# icm_cpld.net
KiCad netlist of a schematic drawn in Altium Designer
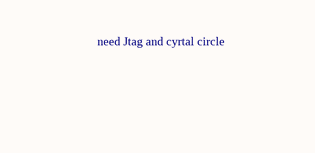
[diagram p0: icm+cpld.SchDoc, top right]
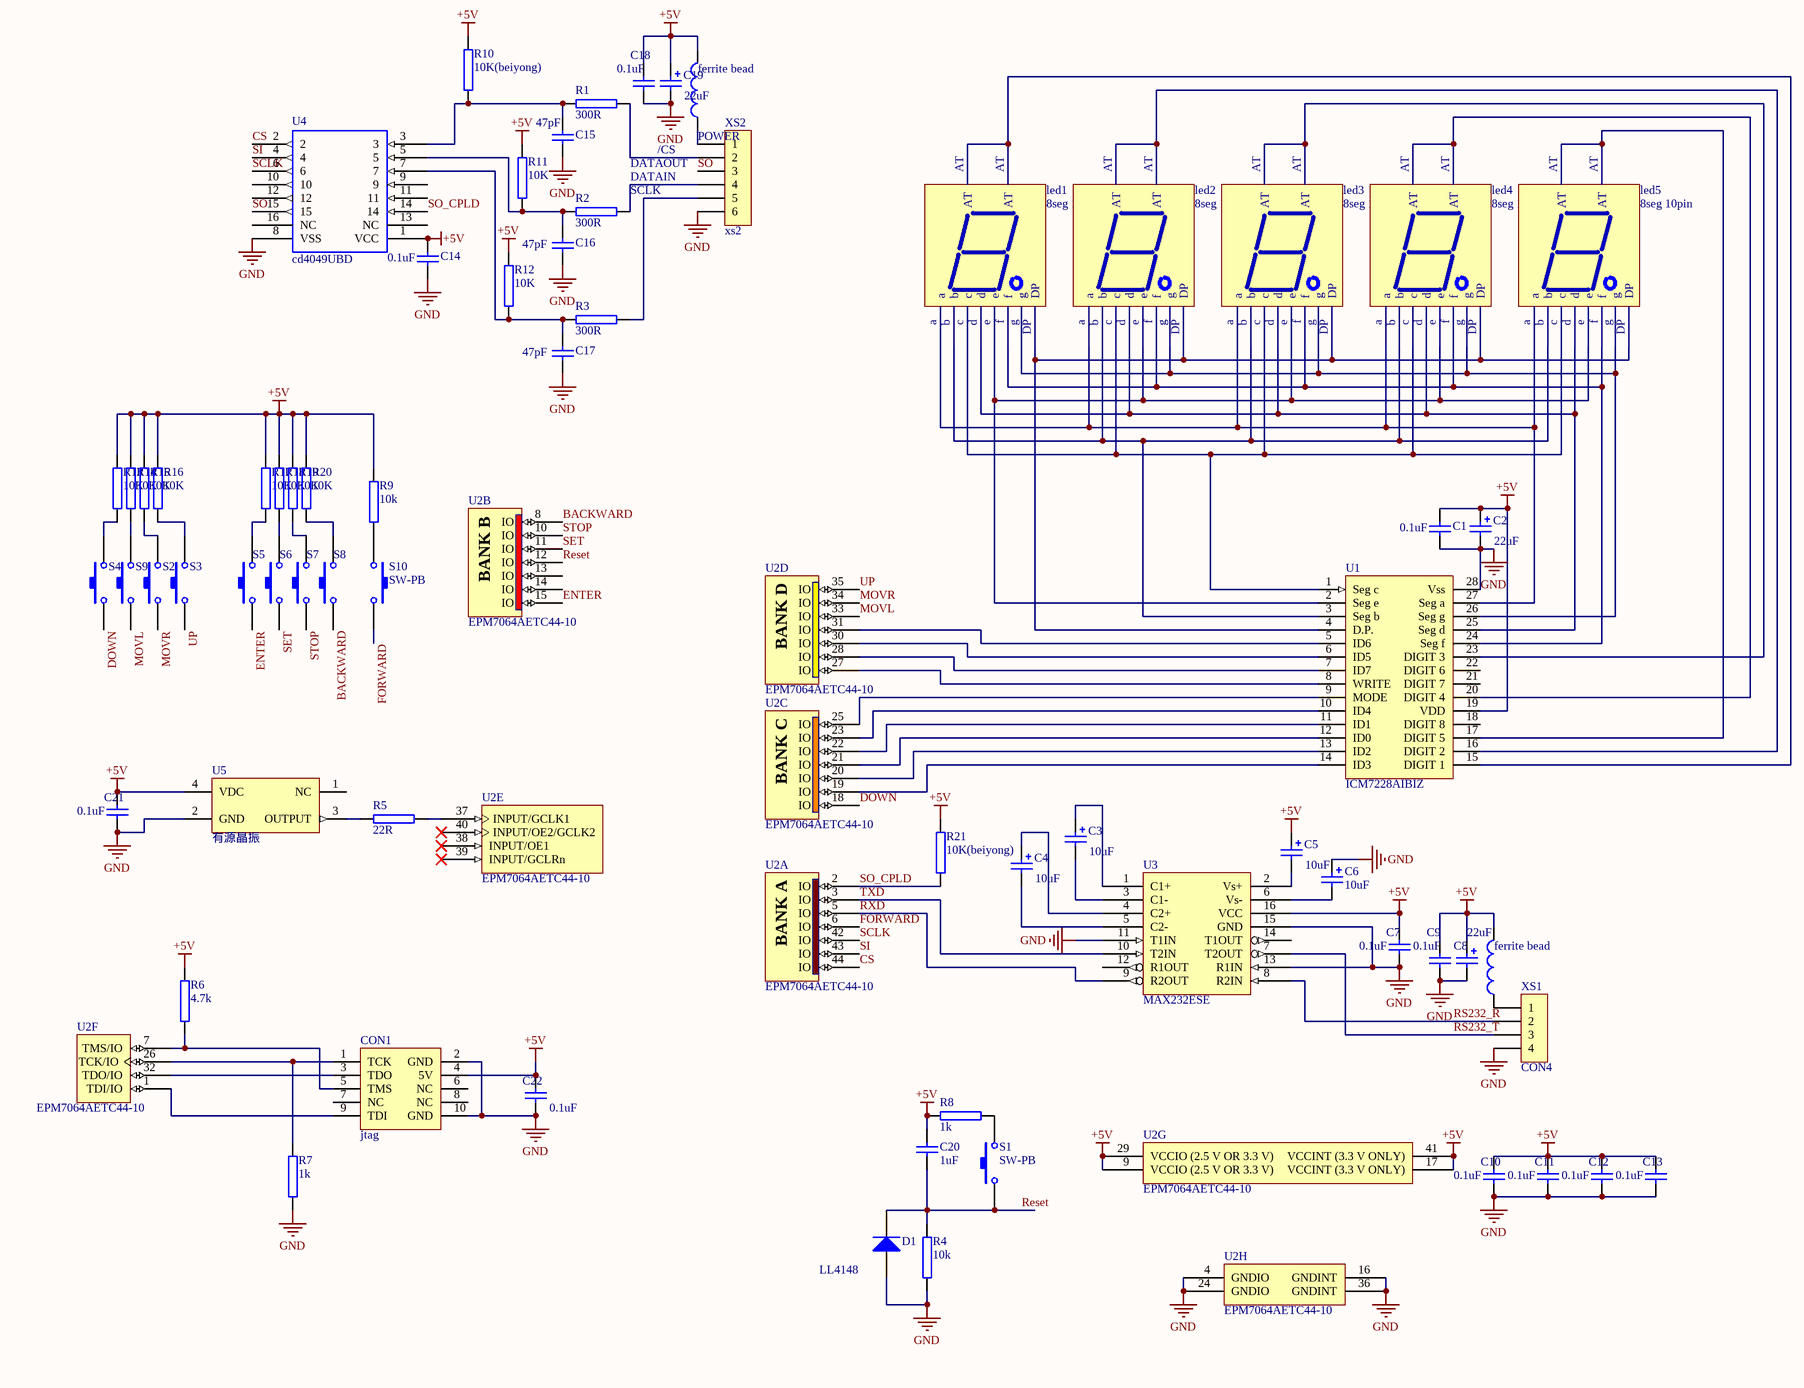
[diagram p1: icm+cpld.SchDoc, bottom left]

(export (version "E")
  (design (tool "Eeschema 10.0.6"))
  (components
    (comp (ref "C1")
      (value "0.1uF")
      (footprint "0805")
      (description "Capacitor")
      (fields (field (name "Comment") "Cap") (field (name "PUBLISHER") "Altium Limited"))
      (libsource (lib "Miscellaneous Devices") (part "Cap"))
    )
    (comp (ref "C2")
      (value "22uF")
      (footprint "7343")
      (description "Polarized Capacitor (Axial)")
      (fields (field (name "PUBLISHER") "Altium Limited"))
      (libsource (lib "Miscellaneous Devices") (part "Cap Pol2"))
    )
    (comp (ref "C3")
      (value "10uF")
      (footprint "C1206")
      (description "Polarized Capacitor (Axial)")
      (fields (field (name "PUBLISHER") "Altium Limited"))
      (libsource (lib "Miscellaneous Devices") (part "Cap Pol2"))
    )
    (comp (ref "C4")
      (value "10uF")
      (footprint "C1206")
      (description "Polarized Capacitor (Axial)")
      (fields (field (name "Comment") "22uF") (field (name "PUBLISHER") "Altium Limited"))
      (libsource (lib "Miscellaneous Devices") (part "Cap Pol2"))
    )
    (comp (ref "C5")
      (value "10uF")
      (footprint "C1206")
      (description "Polarized Capacitor (Axial)")
      (fields (field (name "PUBLISHER") "Altium Limited"))
      (libsource (lib "Miscellaneous Devices") (part "Cap Pol2"))
    )
    (comp (ref "C6")
      (value "10uF")
      (footprint "C1206")
      (description "Polarized Capacitor (Axial)")
      (fields (field (name "PUBLISHER") "Altium Limited"))
      (libsource (lib "Miscellaneous Devices") (part "Cap Pol2"))
    )
    (comp (ref "C7")
      (value "0.1uF")
      (footprint "0805")
      (description "Capacitor")
      (fields (field (name "Comment") "Cap") (field (name "PUBLISHER") "Altium Limited"))
      (libsource (lib "Miscellaneous Devices") (part "Cap"))
    )
    (comp (ref "C8")
      (value "22uF")
      (footprint "7343")
      (description "Polarized Capacitor (Axial)")
      (fields (field (name "PUBLISHER") "Altium Limited"))
      (libsource (lib "Miscellaneous Devices") (part "Cap Pol2"))
    )
    (comp (ref "C9")
      (value "0.1uF")
      (footprint "0805")
      (description "Capacitor")
      (fields (field (name "Comment") "Cap") (field (name "PUBLISHER") "Altium Limited"))
      (libsource (lib "Miscellaneous Devices") (part "Cap"))
    )
    (comp (ref "C10")
      (value "0.1uF")
      (footprint "0805")
      (description "Capacitor")
      (fields (field (name "Comment") "Cap") (field (name "PUBLISHER") "Altium Limited"))
      (libsource (lib "Miscellaneous Devices") (part "Cap"))
    )
    (comp (ref "C11")
      (value "0.1uF")
      (footprint "0805")
      (description "Capacitor")
      (fields (field (name "Comment") "Cap") (field (name "PUBLISHER") "Altium Limited"))
      (libsource (lib "Miscellaneous Devices") (part "Cap"))
    )
    (comp (ref "C12")
      (value "0.1uF")
      (footprint "0805")
      (description "Capacitor")
      (fields (field (name "Comment") "Cap") (field (name "PUBLISHER") "Altium Limited"))
      (libsource (lib "Miscellaneous Devices") (part "Cap"))
    )
    (comp (ref "C13")
      (value "0.1uF")
      (footprint "0805")
      (description "Capacitor")
      (fields (field (name "Comment") "Cap") (field (name "PUBLISHER") "Altium Limited"))
      (libsource (lib "Miscellaneous Devices") (part "Cap"))
    )
    (comp (ref "C14")
      (value "0.1uF")
      (footprint "0805")
      (description "Capacitor")
      (fields (field (name "Comment") "Cap") (field (name "PUBLISHER") "Altium Limited"))
      (libsource (lib "Miscellaneous Devices") (part "Cap"))
    )
    (comp (ref "C15")
      (value "47pF")
      (footprint "0805")
      (description "Capacitor")
      (fields (field (name "Comment") "Cap") (field (name "PUBLISHER") "Altium Limited"))
      (libsource (lib "Miscellaneous Devices") (part "Cap"))
    )
    (comp (ref "C16")
      (value "47pF")
      (footprint "0805")
      (description "Capacitor")
      (fields (field (name "Comment") "Cap") (field (name "PUBLISHER") "Altium Limited"))
      (libsource (lib "Miscellaneous Devices") (part "Cap"))
    )
    (comp (ref "C17")
      (value "47pF")
      (footprint "0805")
      (description "Capacitor")
      (fields (field (name "Comment") "Cap") (field (name "PUBLISHER") "Altium Limited"))
      (libsource (lib "Miscellaneous Devices") (part "Cap"))
    )
    (comp (ref "C18")
      (value "0.1uF")
      (footprint "0805")
      (description "Capacitor")
      (fields (field (name "Comment") "Cap") (field (name "PUBLISHER") "Altium Limited"))
      (libsource (lib "Miscellaneous Devices") (part "Cap"))
    )
    (comp (ref "C19")
      (value "22uF")
      (footprint "7343")
      (description "Polarized Capacitor (Axial)")
      (fields (field (name "PUBLISHER") "Altium Limited"))
      (libsource (lib "Miscellaneous Devices") (part "Cap Pol2"))
    )
    (comp (ref "C20")
      (value "1uF")
      (footprint "1206")
      (description "Capacitor")
      (fields (field (name "Comment") "Cap") (field (name "PUBLISHER") "Altium Limited"))
      (libsource (lib "Miscellaneous Devices") (part "Cap"))
    )
    (comp (ref "C21")
      (value "0.1uF")
      (footprint "0805")
      (description "Capacitor")
      (fields (field (name "Comment") "Cap") (field (name "PUBLISHER") "Altium Limited"))
      (libsource (lib "Miscellaneous Devices") (part "Cap"))
    )
    (comp (ref "C22")
      (value "0.1uF")
      (footprint "0805")
      (description "Capacitor")
      (fields (field (name "Comment") "Cap") (field (name "PUBLISHER") "Altium Limited"))
      (libsource (lib "Miscellaneous Devices") (part "Cap"))
    )
    (comp (ref "CON1") (value "jtag") (footprint "HDR2X5") (libsource (lib "display_1") (part "jtag")))
    (comp (ref "D1")
      (value "LL4148")
      (footprint "DO214")
      (description "High Conductance Fast Diode")
      (fields (field (name "PUBLISHER") "Altium Limited"))
      (libsource (lib "Miscellaneous Devices") (part "Diode 1N4148"))
    )
    (comp (ref "L1") (value "ferrite bead") (footprint "0805") (libsource (lib "display") (part "INDUCTOR")))
    (comp (ref "L2") (value "ferrite bead") (footprint "0805") (libsource (lib "display") (part "INDUCTOR")))
    (comp (ref "led1")
      (value "8seg 10pin")
      (footprint "LEDsum")
      (libsource (lib "display_1") (part "8seg 10pin"))
    )
    (comp (ref "led2")
      (value "8seg 10pin")
      (footprint "LEDsum")
      (libsource (lib "display_1") (part "8seg 10pin"))
    )
    (comp (ref "led3")
      (value "8seg 10pin")
      (footprint "LEDsum")
      (libsource (lib "display_1") (part "8seg 10pin"))
    )
    (comp (ref "led4")
      (value "8seg 10pin")
      (footprint "LEDsum")
      (libsource (lib "display_1") (part "8seg 10pin"))
    )
    (comp (ref "led5")
      (value "8seg 10pin")
      (footprint "LEDsum")
      (libsource (lib "display_1") (part "8seg 10pin"))
    )
    (comp (ref "R1")
      (value "300R")
      (footprint "³£ÓÃÔª¼þ·âÑbì(pcb):0805")
      (libsource (lib "2CPU") (part "RES2"))
    )
    (comp (ref "R2") (value "300R") (footprint "0805") (libsource (lib "2CPU") (part "RES2")))
    (comp (ref "R3") (value "300R") (footprint "0805") (libsource (lib "2CPU") (part "RES2")))
    (comp (ref "R4") (value "10k") (footprint "0805") (libsource (lib "2CPU") (part "RES2")))
    (comp (ref "R5") (value "22R") (footprint "0805") (libsource (lib "2CPU") (part "RES2")))
    (comp (ref "R6") (value "4.7k") (footprint "0805") (libsource (lib "2CPU") (part "RES2")))
    (comp (ref "R7") (value "1k") (footprint "0805") (libsource (lib "2CPU") (part "RES2")))
    (comp (ref "R8") (value "1k") (footprint "0805") (libsource (lib "2CPU") (part "RES2")))
    (comp (ref "R9") (value "10k") (footprint "0805") (libsource (lib "2CPU") (part "RES2")))
    (comp (ref "R10")
      (value "10K(beiyong)")
      (footprint "³£ÓÃÔª¼þ·âÑbì(pcb):0805")
      (libsource (lib "2CPU") (part "RES2"))
    )
    (comp (ref "R11")
      (value "10K")
      (footprint "³£ÓÃÔª¼þ·âÑbì(pcb):0805")
      (libsource (lib "2CPU") (part "RES2"))
    )
    (comp (ref "R12")
      (value "10K")
      (footprint "³£ÓÃÔª¼þ·âÑbì(pcb):0805")
      (libsource (lib "2CPU") (part "RES2"))
    )
    (comp (ref "R13")
      (value "10K")
      (footprint "³£ÓÃÔª¼þ·âÑbì(pcb):0805")
      (libsource (lib "2CPU") (part "RES2"))
    )
    (comp (ref "R14")
      (value "10K")
      (footprint "³£ÓÃÔª¼þ·âÑbì(pcb):0805")
      (libsource (lib "2CPU") (part "RES2"))
    )
    (comp (ref "R15")
      (value "10K")
      (footprint "³£ÓÃÔª¼þ·âÑbì(pcb):0805")
      (libsource (lib "2CPU") (part "RES2"))
    )
    (comp (ref "R16")
      (value "10K")
      (footprint "³£ÓÃÔª¼þ·âÑbì(pcb):0805")
      (libsource (lib "2CPU") (part "RES2"))
    )
    (comp (ref "R17")
      (value "10K")
      (footprint "³£ÓÃÔª¼þ·âÑbì(pcb):0805")
      (libsource (lib "2CPU") (part "RES2"))
    )
    (comp (ref "R18")
      (value "10K")
      (footprint "³£ÓÃÔª¼þ·âÑbì(pcb):0805")
      (libsource (lib "2CPU") (part "RES2"))
    )
    (comp (ref "R19")
      (value "10K")
      (footprint "³£ÓÃÔª¼þ·âÑbì(pcb):0805")
      (libsource (lib "2CPU") (part "RES2"))
    )
    (comp (ref "R20")
      (value "10K")
      (footprint "³£ÓÃÔª¼þ·âÑbì(pcb):0805")
      (libsource (lib "2CPU") (part "RES2"))
    )
    (comp (ref "R21")
      (value "10K(beiyong)")
      (footprint "³£ÓÃÔª¼þ·âÑbì(pcb):0805")
      (libsource (lib "2CPU") (part "RES2"))
    )
    (comp (ref "S1")
      (value "SW-PB")
      (footprint "PcbLib1:reset")
      (description "Switch")
      (fields (field (name "PUBLISHER") "Altium Limited"))
      (libsource (lib "Miscellaneous Devices") (part "SW-PB"))
    )
    (comp (ref "S2")
      (value "SW-PB")
      (footprint "PcbLib1:B3F4050")
      (description "Switch")
      (fields (field (name "PUBLISHER") "Altium Limited"))
      (libsource (lib "Miscellaneous Devices") (part "SW-PB"))
    )
    (comp (ref "S3")
      (value "SW-PB")
      (footprint "PcbLib1:B3F4050")
      (description "Switch")
      (fields (field (name "PUBLISHER") "Altium Limited"))
      (libsource (lib "Miscellaneous Devices") (part "SW-PB"))
    )
    (comp (ref "S4")
      (value "SW-PB")
      (footprint "PcbLib1:B3F4050")
      (description "Switch")
      (fields (field (name "PUBLISHER") "Altium Limited"))
      (libsource (lib "Miscellaneous Devices") (part "SW-PB"))
    )
    (comp (ref "S5")
      (value "SW-PB")
      (footprint "PcbLib1:B3F4050")
      (description "Switch")
      (fields (field (name "PUBLISHER") "Altium Limited"))
      (libsource (lib "Miscellaneous Devices") (part "SW-PB"))
    )
    (comp (ref "S6")
      (value "SW-PB")
      (footprint "PcbLib1:B3F4050")
      (description "Switch")
      (fields (field (name "PUBLISHER") "Altium Limited"))
      (libsource (lib "Miscellaneous Devices") (part "SW-PB"))
    )
    (comp (ref "S7")
      (value "SW-PB")
      (footprint "PcbLib1:B3F4050")
      (description "Switch")
      (fields (field (name "PUBLISHER") "Altium Limited"))
      (libsource (lib "Miscellaneous Devices") (part "SW-PB"))
    )
    (comp (ref "S8")
      (value "SW-PB")
      (footprint "PcbLib1:B3F4050")
      (description "Switch")
      (fields (field (name "PUBLISHER") "Altium Limited"))
      (libsource (lib "Miscellaneous Devices") (part "SW-PB"))
    )
    (comp (ref "S9")
      (value "SW-PB")
      (footprint "PcbLib1:B3F4050")
      (description "Switch")
      (fields (field (name "PUBLISHER") "Altium Limited"))
      (libsource (lib "Miscellaneous Devices") (part "SW-PB"))
    )
    (comp (ref "S10")
      (value "SW-PB")
      (footprint "B3F4050")
      (description "Switch")
      (fields (field (name "PUBLISHER") "Altium Limited"))
      (libsource (lib "Miscellaneous Devices") (part "SW-PB"))
    )
    (comp (ref "U1") (value "ICM7228AIBIZ") (footprint "SO28_L") (libsource (lib "lib") (part "ICM7218")))
    (comp (ref "U2")
      (value "EPM7064AETC44-10")
      (footprint "TQFP44_N")
      (description "MAX 7000AE 3.3V CPLD, 64 Macrocells, 44-Pin TQFP, Speed Grade 10, Commercial Grade")
      (fields (field (name "PUBLISHER") "Altium Limited"))
      (libsource (lib "Altera MAX 7000AE") (part "EPM7064AETC44-10"))
    )
    (comp (ref "U3")
      (value "MAX232ESE")
      (footprint "NSO16_N")
      (description "DUAL EIA-232 DRIVER/RECEIVER")
      (libsource (lib "2CPU") (part "MAX232"))
    )
    (comp (ref "U4") (value "cd4049UBD") (footprint "L16_N") (libsource (lib "display_1") (part "cd4049")))
    (comp (ref "U5") (value "有源晶振") (footprint "smd7050") (libsource (lib "display_1") (part "jingzhen")))
    (comp (ref "XS1")
      (value "CON4")
      (footprint "2SIP4")
      (description "Connector")
      (libsource (lib "2CPU") (part "CON4"))
    )
    (comp (ref "XS2") (value "xs2") (footprint "SIP6") (libsource (lib "display") (part "xs6")))
  )
  (nets
    (net (code "1") (name "+5V") (class "Default")
      (node (ref "C1") (pin "2") (pinfunction "2_2") (pintype "passive"))
      (node (ref "C10") (pin "2") (pinfunction "2_2") (pintype "passive"))
      (node (ref "C11") (pin "2") (pinfunction "2_2") (pintype "passive"))
      (node (ref "C12") (pin "2") (pinfunction "2_2") (pintype "passive"))
      (node (ref "C13") (pin "2") (pinfunction "2_2") (pintype "passive"))
      (node (ref "C14") (pin "2") (pinfunction "2_2") (pintype "passive"))
      (node (ref "C18") (pin "2") (pinfunction "2_2") (pintype "passive"))
      (node (ref "C19") (pin "1") (pinfunction "1_1") (pintype "passive"))
      (node (ref "C2") (pin "1") (pinfunction "1_1") (pintype "passive"))
      (node (ref "C20") (pin "1") (pinfunction "1_1") (pintype "passive"))
      (node (ref "C21") (pin "2") (pinfunction "2_2") (pintype "passive"))
      (node (ref "C22") (pin "2") (pinfunction "2_2") (pintype "passive"))
      (node (ref "C5") (pin "1") (pinfunction "1_1") (pintype "passive"))
      (node (ref "C7") (pin "2") (pinfunction "2_2") (pintype "passive"))
      (node (ref "C8") (pin "1") (pinfunction "1_1") (pintype "passive"))
      (node (ref "C9") (pin "2") (pinfunction "2_2") (pintype "passive"))
      (node (ref "CON1") (pin "4") (pinfunction "5V_4") (pintype "power_in"))
      (node (ref "L1") (pin "1") (pinfunction "1_1") (pintype "passive"))
      (node (ref "L2") (pin "1") (pinfunction "1_1") (pintype "passive"))
      (node (ref "R10") (pin "2") (pinfunction "2_2") (pintype "passive"))
      (node (ref "R11") (pin "2") (pinfunction "2_2") (pintype "passive"))
      (node (ref "R12") (pin "2") (pinfunction "2_2") (pintype "passive"))
      (node (ref "R13") (pin "2") (pinfunction "2_2") (pintype "passive"))
      (node (ref "R14") (pin "2") (pinfunction "2_2") (pintype "passive"))
      (node (ref "R15") (pin "2") (pinfunction "2_2") (pintype "passive"))
      (node (ref "R16") (pin "2") (pinfunction "2_2") (pintype "passive"))
      (node (ref "R17") (pin "2") (pinfunction "2_2") (pintype "passive"))
      (node (ref "R18") (pin "2") (pinfunction "2_2") (pintype "passive"))
      (node (ref "R19") (pin "2") (pinfunction "2_2") (pintype "passive"))
      (node (ref "R20") (pin "2") (pinfunction "2_2") (pintype "passive"))
      (node (ref "R21") (pin "2") (pinfunction "2_2") (pintype "passive"))
      (node (ref "R6") (pin "1") (pinfunction "1_1") (pintype "passive"))
      (node (ref "R8") (pin "2") (pinfunction "2_2") (pintype "passive"))
      (node (ref "R9") (pin "1") (pinfunction "1_1") (pintype "passive"))
      (node (ref "U1") (pin "19") (pinfunction "VDD_19") (pintype "passive"))
      (node (ref "U2") (pin "17") (pinfunction "VCCINT_(3.3_V_ONLY)_17") (pintype "power_in"))
      (node (ref "U2") (pin "29") (pinfunction "VCCIO_(2.5_V_OR_3.3_V)_29") (pintype "power_in"))
      (node (ref "U2") (pin "41") (pinfunction "VCCINT_(3.3_V_ONLY)_41") (pintype "power_in"))
      (node (ref "U2") (pin "9") (pinfunction "VCCIO_(2.5_V_OR_3.3_V)_9") (pintype "power_in"))
      (node (ref "U3") (pin "16") (pinfunction "VCC_16") (pintype "power_in"))
      (node (ref "U4") (pin "1") (pinfunction "VCC_1") (pintype "power_in"))
      (node (ref "U5") (pin "4") (pinfunction "VDC_4") (pintype "power_in"))
    )
    (net (code "2") (name "/BACKWARD") (class "Default")
      (node (ref "S8") (pin "1") (pinfunction "1_1") (pintype "passive"))
      (node (ref "U2") (pin "8") (pinfunction "IO_8") (pintype "bidirectional"))
    )
    (net (code "3") (name "/CS") (class "Default")
      (node (ref "U2") (pin "44") (pinfunction "IO_44") (pintype "bidirectional"))
      (node (ref "U4") (pin "2") (pinfunction "2_2") (pintype "output"))
    )
    (net (code "4") (name "/DOWN") (class "Default")
      (node (ref "S4") (pin "1") (pinfunction "1_1") (pintype "passive"))
      (node (ref "U2") (pin "18") (pinfunction "IO_18") (pintype "bidirectional"))
    )
    (net (code "5") (name "/ENTER") (class "Default")
      (node (ref "S5") (pin "1") (pinfunction "1_1") (pintype "passive"))
      (node (ref "U2") (pin "15") (pinfunction "IO_15") (pintype "bidirectional"))
    )
    (net (code "6") (name "/FORWARD") (class "Default")
      (node (ref "S10") (pin "2") (pinfunction "2_2") (pintype "passive"))
      (node (ref "U2") (pin "6") (pinfunction "IO_6") (pintype "bidirectional"))
    )
    (net (code "7") (name "/MOVL") (class "Default")
      (node (ref "S9") (pin "1") (pinfunction "1_1") (pintype "passive"))
      (node (ref "U2") (pin "33") (pinfunction "IO_33") (pintype "bidirectional"))
    )
    (net (code "8") (name "/MOVR") (class "Default")
      (node (ref "S2") (pin "1") (pinfunction "1_1") (pintype "passive"))
      (node (ref "U2") (pin "34") (pinfunction "IO_34") (pintype "bidirectional"))
    )
    (net (code "9") (name "/RS232_R") (class "Default")
      (node (ref "U3") (pin "8") (pinfunction "R2IN_8") (pintype "input"))
      (node (ref "XS1") (pin "2") (pinfunction "2_2") (pintype "passive"))
    )
    (net (code "10") (name "/RS232_T") (class "Default")
      (node (ref "U3") (pin "7") (pinfunction "T2OUT_7") (pintype "output"))
      (node (ref "XS1") (pin "3") (pinfunction "3_3") (pintype "passive"))
    )
    (net (code "11") (name "/RXD") (class "Default")
      (node (ref "U2") (pin "5") (pinfunction "IO_5") (pintype "bidirectional"))
      (node (ref "U3") (pin "9") (pinfunction "R2OUT_9") (pintype "output"))
    )
    (net (code "12") (name "/Reset") (class "Default")
      (node (ref "C20") (pin "2") (pinfunction "2_2") (pintype "passive"))
      (node (ref "D1") (pin "2") (pinfunction "K_2") (pintype "passive"))
      (node (ref "R4") (pin "2") (pinfunction "2_2") (pintype "passive"))
      (node (ref "S1") (pin "1") (pinfunction "1_1") (pintype "passive"))
      (node (ref "U2") (pin "12") (pinfunction "IO_12") (pintype "bidirectional"))
    )
    (net (code "13") (name "/SCLK") (class "Default")
      (node (ref "U2") (pin "42") (pinfunction "IO_42") (pintype "bidirectional"))
      (node (ref "U4") (pin "6") (pinfunction "6_6") (pintype "output"))
    )
    (net (code "14") (name "/SET") (class "Default")
      (node (ref "S6") (pin "1") (pinfunction "1_1") (pintype "passive"))
      (node (ref "U2") (pin "11") (pinfunction "IO_11") (pintype "bidirectional"))
    )
    (net (code "15") (name "/SI") (class "Default")
      (node (ref "U2") (pin "43") (pinfunction "IO_43") (pintype "bidirectional"))
      (node (ref "U4") (pin "4") (pinfunction "4_4") (pintype "output"))
    )
    (net (code "16") (name "/SO") (class "Default")
      (node (ref "U4") (pin "15") (pinfunction "15_15") (pintype "output"))
      (node (ref "XS2") (pin "3") (pinfunction "3_3") (pintype "passive"))
    )
    (net (code "17") (name "/SO_CPLD") (class "Default")
      (node (ref "R21") (pin "1") (pinfunction "1_1") (pintype "passive"))
      (node (ref "U2") (pin "2") (pinfunction "IO_2") (pintype "bidirectional"))
      (node (ref "U4") (pin "14") (pinfunction "14_14") (pintype "input"))
    )
    (net (code "18") (name "/STOP") (class "Default")
      (node (ref "S7") (pin "1") (pinfunction "1_1") (pintype "passive"))
      (node (ref "U2") (pin "10") (pinfunction "IO_10") (pintype "bidirectional"))
    )
    (net (code "19") (name "/TXD") (class "Default")
      (node (ref "U2") (pin "3") (pinfunction "IO_3") (pintype "bidirectional"))
      (node (ref "U3") (pin "10") (pinfunction "T2IN_10") (pintype "input"))
    )
    (net (code "20") (name "/UP") (class "Default")
      (node (ref "S3") (pin "1") (pinfunction "1_1") (pintype "passive"))
      (node (ref "U2") (pin "35") (pinfunction "IO_35") (pintype "bidirectional"))
    )
    (net (code "21") (name "GND") (class "Default")
      (node (ref "C1") (pin "1") (pinfunction "1_1") (pintype "passive"))
      (node (ref "C10") (pin "1") (pinfunction "1_1") (pintype "passive"))
      (node (ref "C11") (pin "1") (pinfunction "1_1") (pintype "passive"))
      (node (ref "C12") (pin "1") (pinfunction "1_1") (pintype "passive"))
      (node (ref "C13") (pin "1") (pinfunction "1_1") (pintype "passive"))
      (node (ref "C14") (pin "1") (pinfunction "1_1") (pintype "passive"))
      (node (ref "C15") (pin "1") (pinfunction "1_1") (pintype "passive"))
      (node (ref "C16") (pin "1") (pinfunction "1_1") (pintype "passive"))
      (node (ref "C17") (pin "1") (pinfunction "1_1") (pintype "passive"))
      (node (ref "C18") (pin "1") (pinfunction "1_1") (pintype "passive"))
      (node (ref "C19") (pin "2") (pinfunction "2_2") (pintype "passive"))
      (node (ref "C2") (pin "2") (pinfunction "2_2") (pintype "passive"))
      (node (ref "C21") (pin "1") (pinfunction "1_1") (pintype "passive"))
      (node (ref "C22") (pin "1") (pinfunction "1_1") (pintype "passive"))
      (node (ref "C6") (pin "1") (pinfunction "1_1") (pintype "passive"))
      (node (ref "C7") (pin "1") (pinfunction "1_1") (pintype "passive"))
      (node (ref "C8") (pin "2") (pinfunction "2_2") (pintype "passive"))
      (node (ref "C9") (pin "1") (pinfunction "1_1") (pintype "passive"))
      (node (ref "CON1") (pin "10") (pinfunction "GND_10") (pintype "power_in"))
      (node (ref "CON1") (pin "2") (pinfunction "GND_2") (pintype "power_in"))
      (node (ref "D1") (pin "1") (pinfunction "A_1") (pintype "passive"))
      (node (ref "R4") (pin "1") (pinfunction "1_1") (pintype "passive"))
      (node (ref "R7") (pin "2") (pinfunction "2_2") (pintype "passive"))
      (node (ref "U1") (pin "28") (pinfunction "Vss_28") (pintype "passive"))
      (node (ref "U2") (pin "16") (pinfunction "GNDINT_16") (pintype "power_in"))
      (node (ref "U2") (pin "24") (pinfunction "GNDIO_24") (pintype "power_in"))
      (node (ref "U2") (pin "36") (pinfunction "GNDINT_36") (pintype "power_in"))
      (node (ref "U2") (pin "4") (pinfunction "GNDIO_4") (pintype "power_in"))
      (node (ref "U3") (pin "11") (pinfunction "T1IN_11") (pintype "input"))
      (node (ref "U3") (pin "13") (pinfunction "R1IN_13") (pintype "input"))
      (node (ref "U3") (pin "15") (pinfunction "GND_15") (pintype "power_in"))
      (node (ref "U4") (pin "8") (pinfunction "VSS_8") (pintype "power_in"))
      (node (ref "U5") (pin "2") (pinfunction "GND_2") (pintype "power_in"))
      (node (ref "XS1") (pin "4") (pinfunction "4_4") (pintype "passive"))
      (node (ref "XS2") (pin "6") (pinfunction "6_6") (pintype "passive"))
    )
    (net (code "22") (name "Net-(C15-Pad2)") (class "Default")
      (node (ref "C15") (pin "2") (pinfunction "2_2") (pintype "passive"))
      (node (ref "R1") (pin "1") (pinfunction "1_1") (pintype "passive"))
      (node (ref "R10") (pin "1") (pinfunction "1_1") (pintype "passive"))
      (node (ref "U4") (pin "3") (pinfunction "3_3") (pintype "input"))
    )
    (net (code "23") (name "Net-(C16-Pad2)") (class "Default")
      (node (ref "C16") (pin "2") (pinfunction "2_2") (pintype "passive"))
      (node (ref "R11") (pin "1") (pinfunction "1_1") (pintype "passive"))
      (node (ref "R2") (pin "1") (pinfunction "1_1") (pintype "passive"))
      (node (ref "U4") (pin "5") (pinfunction "5_5") (pintype "input"))
    )
    (net (code "24") (name "Net-(C17-Pad2)") (class "Default")
      (node (ref "C17") (pin "2") (pinfunction "2_2") (pintype "passive"))
      (node (ref "R12") (pin "1") (pinfunction "1_1") (pintype "passive"))
      (node (ref "R3") (pin "1") (pinfunction "1_1") (pintype "passive"))
      (node (ref "U4") (pin "7") (pinfunction "7_7") (pintype "input"))
    )
    (net (code "25") (name "Net-(CON1-TCK)") (class "Default")
      (node (ref "CON1") (pin "1") (pinfunction "TCK_1") (pintype "passive"))
      (node (ref "R7") (pin "1") (pinfunction "1_1") (pintype "passive"))
      (node (ref "U2") (pin "26") (pinfunction "TCK/IO_26") (pintype "bidirectional"))
    )
    (net (code "26") (name "Net-(CON1-TDI)") (class "Default")
      (node (ref "CON1") (pin "9") (pinfunction "TDI_9") (pintype "passive"))
      (node (ref "U2") (pin "1") (pinfunction "TDI/IO_1") (pintype "bidirectional"))
    )
    (net (code "27") (name "Net-(CON1-TDO)") (class "Default")
      (node (ref "CON1") (pin "3") (pinfunction "TDO_3") (pintype "passive"))
      (node (ref "U2") (pin "32") (pinfunction "TDO/IO_32") (pintype "bidirectional"))
    )
    (net (code "28") (name "Net-(CON1-TMS)") (class "Default")
      (node (ref "CON1") (pin "5") (pinfunction "TMS_5") (pintype "passive"))
      (node (ref "R6") (pin "2") (pinfunction "2_2") (pintype "passive"))
      (node (ref "U2") (pin "7") (pinfunction "TMS/IO_7") (pintype "bidirectional"))
    )
    (net (code "29") (name "Net-(L1-Pad2)") (class "Default")
      (node (ref "L1") (pin "2") (pinfunction "2_2") (pintype "passive"))
      (node (ref "XS1") (pin "1") (pinfunction "1_1") (pintype "passive"))
    )
    (net (code "30") (name "Net-(L2-Pad2)") (class "Default")
      (node (ref "L2") (pin "2") (pinfunction "2_2") (pintype "passive"))
      (node (ref "XS2") (pin "1") (pinfunction "1_1") (pintype "passive"))
    )
    (net (code "31") (name "Net-(R1-Pad2)") (class "Default")
      (node (ref "R1") (pin "2") (pinfunction "2_2") (pintype "passive"))
      (node (ref "XS2") (pin "2") (pinfunction "2_2") (pintype "passive"))
    )
    (net (code "32") (name "Net-(R2-Pad2)") (class "Default")
      (node (ref "R2") (pin "2") (pinfunction "2_2") (pintype "passive"))
      (node (ref "XS2") (pin "4") (pinfunction "4_4") (pintype "passive"))
    )
    (net (code "33") (name "Net-(R3-Pad2)") (class "Default")
      (node (ref "R3") (pin "2") (pinfunction "2_2") (pintype "passive"))
      (node (ref "XS2") (pin "5") (pinfunction "5_5") (pintype "passive"))
    )
    (net (code "34") (name "Net-(R8-Pad1)") (class "Default")
      (node (ref "R8") (pin "1") (pinfunction "1_1") (pintype "passive"))
      (node (ref "S1") (pin "2") (pinfunction "2_2") (pintype "passive"))
    )
    (net (code "35") (name "Net-(R9-Pad2)") (class "Default")
      (node (ref "R9") (pin "2") (pinfunction "2_2") (pintype "passive"))
      (node (ref "S10") (pin "1") (pinfunction "1_1") (pintype "passive"))
    )
    (net (code "36") (name "Net-(R13-Pad1)") (class "Default")
      (node (ref "R13") (pin "1") (pinfunction "1_1") (pintype "passive"))
      (node (ref "S4") (pin "2") (pinfunction "2_2") (pintype "passive"))
    )
    (net (code "37") (name "Net-(R14-Pad1)") (class "Default")
      (node (ref "R14") (pin "1") (pinfunction "1_1") (pintype "passive"))
      (node (ref "S9") (pin "2") (pinfunction "2_2") (pintype "passive"))
    )
    (net (code "38") (name "Net-(R15-Pad1)") (class "Default")
      (node (ref "R15") (pin "1") (pinfunction "1_1") (pintype "passive"))
      (node (ref "S2") (pin "2") (pinfunction "2_2") (pintype "passive"))
    )
    (net (code "39") (name "Net-(R16-Pad1)") (class "Default")
      (node (ref "R16") (pin "1") (pinfunction "1_1") (pintype "passive"))
      (node (ref "S3") (pin "2") (pinfunction "2_2") (pintype "passive"))
    )
    (net (code "40") (name "Net-(R17-Pad1)") (class "Default")
      (node (ref "R17") (pin "1") (pinfunction "1_1") (pintype "passive"))
      (node (ref "S5") (pin "2") (pinfunction "2_2") (pintype "passive"))
    )
    (net (code "41") (name "Net-(R18-Pad1)") (class "Default")
      (node (ref "R18") (pin "1") (pinfunction "1_1") (pintype "passive"))
      (node (ref "S6") (pin "2") (pinfunction "2_2") (pintype "passive"))
    )
    (net (code "42") (name "Net-(R19-Pad1)") (class "Default")
      (node (ref "R19") (pin "1") (pinfunction "1_1") (pintype "passive"))
      (node (ref "S7") (pin "2") (pinfunction "2_2") (pintype "passive"))
    )
    (net (code "43") (name "Net-(R20-Pad1)") (class "Default")
      (node (ref "R20") (pin "1") (pinfunction "1_1") (pintype "passive"))
      (node (ref "S8") (pin "2") (pinfunction "2_2") (pintype "passive"))
    )
    (net (code "44") (name "Net-(U1-D.P.)") (class "Default")
      (node (ref "U1") (pin "4") (pinfunction "D.P._4") (pintype "passive"))
      (node (ref "led1") (pin "DP") (pinfunction "DP_DP") (pintype "passive"))
      (node (ref "led2") (pin "DP") (pinfunction "DP_DP") (pintype "passive"))
      (node (ref "led3") (pin "DP") (pinfunction "DP_DP") (pintype "passive"))
      (node (ref "led4") (pin "DP") (pinfunction "DP_DP") (pintype "passive"))
      (node (ref "led5") (pin "DP") (pinfunction "DP_DP") (pintype "passive"))
    )
    (net (code "45") (name "Net-(U1-DIGIT_1)") (class "Default")
      (node (ref "U1") (pin "15") (pinfunction "DIGIT_1_15") (pintype "passive"))
      (node (ref "led1") (pin "AT") (pinfunction "AT_AT") (pintype "passive"))
    )
    (net (code "46") (name "Net-(U1-DIGIT_2)") (class "Default")
      (node (ref "U1") (pin "16") (pinfunction "DIGIT_2_16") (pintype "passive"))
      (node (ref "led2") (pin "AT") (pinfunction "AT_AT") (pintype "passive"))
    )
    (net (code "47") (name "Net-(U1-DIGIT_3)") (class "Default")
      (node (ref "U1") (pin "23") (pinfunction "DIGIT_3_23") (pintype "passive"))
      (node (ref "led3") (pin "AT") (pinfunction "AT_AT") (pintype "passive"))
    )
    (net (code "48") (name "Net-(U1-DIGIT_4)") (class "Default")
      (node (ref "U1") (pin "20") (pinfunction "DIGIT_4_20") (pintype "passive"))
      (node (ref "led4") (pin "AT") (pinfunction "AT_AT") (pintype "passive"))
    )
    (net (code "49") (name "Net-(U1-DIGIT_5)") (class "Default")
      (node (ref "U1") (pin "17") (pinfunction "DIGIT_5_17") (pintype "passive"))
      (node (ref "led5") (pin "AT") (pinfunction "AT_AT") (pintype "passive"))
    )
    (net (code "50") (name "Net-(U1-ID0)") (class "Default")
      (node (ref "U1") (pin "12") (pinfunction "ID0_12") (pintype "passive"))
      (node (ref "U2") (pin "21") (pinfunction "IO_21") (pintype "bidirectional"))
    )
    (net (code "51") (name "Net-(U1-ID1)") (class "Default")
      (node (ref "U1") (pin "11") (pinfunction "ID1_11") (pintype "passive"))
      (node (ref "U2") (pin "22") (pinfunction "IO_22") (pintype "bidirectional"))
    )
    (net (code "52") (name "Net-(U1-ID2)") (class "Default")
      (node (ref "U1") (pin "13") (pinfunction "ID2_13") (pintype "passive"))
      (node (ref "U2") (pin "20") (pinfunction "IO_20") (pintype "bidirectional"))
    )
    (net (code "53") (name "Net-(U1-ID3)") (class "Default")
      (node (ref "U1") (pin "14") (pinfunction "ID3_14") (pintype "passive"))
      (node (ref "U2") (pin "19") (pinfunction "IO_19") (pintype "bidirectional"))
    )
    (net (code "54") (name "Net-(U1-ID4)") (class "Default")
      (node (ref "U1") (pin "10") (pinfunction "ID4_10") (pintype "passive"))
      (node (ref "U2") (pin "23") (pinfunction "IO_23") (pintype "bidirectional"))
    )
    (net (code "55") (name "Net-(U1-ID5)") (class "Default")
      (node (ref "U1") (pin "6") (pinfunction "ID5_6") (pintype "passive"))
      (node (ref "U2") (pin "30") (pinfunction "IO_30") (pintype "bidirectional"))
    )
    (net (code "56") (name "Net-(U1-ID6)") (class "Default")
      (node (ref "U1") (pin "5") (pinfunction "ID6_5") (pintype "passive"))
      (node (ref "U2") (pin "31") (pinfunction "IO_31") (pintype "bidirectional"))
    )
    (net (code "57") (name "Net-(U1-ID7)") (class "Default")
      (node (ref "U1") (pin "7") (pinfunction "ID7_7") (pintype "passive"))
      (node (ref "U2") (pin "28") (pinfunction "IO_28") (pintype "bidirectional"))
    )
    (net (code "58") (name "Net-(U1-MODE)") (class "Default")
      (node (ref "U1") (pin "9") (pinfunction "MODE_9") (pintype "passive"))
      (node (ref "U2") (pin "25") (pinfunction "IO_25") (pintype "bidirectional"))
    )
    (net (code "59") (name "Net-(U1-Seg_a)") (class "Default")
      (node (ref "U1") (pin "27") (pinfunction "Seg_a_27") (pintype "passive"))
      (node (ref "led1") (pin "a") (pinfunction "a_a") (pintype "passive"))
      (node (ref "led2") (pin "a") (pinfunction "a_a") (pintype "passive"))
      (node (ref "led3") (pin "a") (pinfunction "a_a") (pintype "passive"))
      (node (ref "led4") (pin "a") (pinfunction "a_a") (pintype "passive"))
      (node (ref "led5") (pin "a") (pinfunction "a_a") (pintype "passive"))
    )
    (net (code "60") (name "Net-(U1-Seg_b)") (class "Default")
      (node (ref "U1") (pin "3") (pinfunction "Seg_b_3") (pintype "passive"))
      (node (ref "led1") (pin "b") (pinfunction "b_b") (pintype "passive"))
      (node (ref "led2") (pin "b") (pinfunction "b_b") (pintype "passive"))
      (node (ref "led3") (pin "b") (pinfunction "b_b") (pintype "passive"))
      (node (ref "led4") (pin "b") (pinfunction "b_b") (pintype "passive"))
      (node (ref "led5") (pin "b") (pinfunction "b_b") (pintype "passive"))
    )
    (net (code "61") (name "Net-(U1-Seg_c)") (class "Default")
      (node (ref "U1") (pin "1") (pinfunction "Seg_c_1") (pintype "input"))
      (node (ref "led1") (pin "c") (pinfunction "c_c") (pintype "passive"))
      (node (ref "led2") (pin "c") (pinfunction "c_c") (pintype "passive"))
      (node (ref "led3") (pin "c") (pinfunction "c_c") (pintype "passive"))
      (node (ref "led4") (pin "c") (pinfunction "c_c") (pintype "passive"))
      (node (ref "led5") (pin "c") (pinfunction "c_c") (pintype "passive"))
    )
    (net (code "62") (name "Net-(U1-Seg_d)") (class "Default")
      (node (ref "U1") (pin "25") (pinfunction "Seg_d_25") (pintype "passive"))
      (node (ref "led1") (pin "d") (pinfunction "d_d") (pintype "passive"))
      (node (ref "led2") (pin "d") (pinfunction "d_d") (pintype "passive"))
      (node (ref "led3") (pin "d") (pinfunction "d_d") (pintype "passive"))
      (node (ref "led4") (pin "d") (pinfunction "d_d") (pintype "passive"))
      (node (ref "led5") (pin "d") (pinfunction "d_d") (pintype "passive"))
    )
    (net (code "63") (name "Net-(U1-Seg_e)") (class "Default")
      (node (ref "U1") (pin "2") (pinfunction "Seg_e_2") (pintype "passive"))
      (node (ref "led1") (pin "e") (pinfunction "e_e") (pintype "passive"))
      (node (ref "led2") (pin "e") (pinfunction "e_e") (pintype "passive"))
      (node (ref "led3") (pin "e") (pinfunction "e_e") (pintype "passive"))
      (node (ref "led4") (pin "e") (pinfunction "e_e") (pintype "passive"))
      (node (ref "led5") (pin "e") (pinfunction "e_e") (pintype "passive"))
    )
    (net (code "64") (name "Net-(U1-Seg_f)") (class "Default")
      (node (ref "U1") (pin "24") (pinfunction "Seg_f_24") (pintype "passive"))
      (node (ref "led1") (pin "f") (pinfunction "f_f") (pintype "passive"))
      (node (ref "led2") (pin "f") (pinfunction "f_f") (pintype "passive"))
      (node (ref "led3") (pin "f") (pinfunction "f_f") (pintype "passive"))
      (node (ref "led4") (pin "f") (pinfunction "f_f") (pintype "passive"))
      (node (ref "led5") (pin "f") (pinfunction "f_f") (pintype "passive"))
    )
    (net (code "65") (name "Net-(U1-Seg_g)") (class "Default")
      (node (ref "U1") (pin "26") (pinfunction "Seg_g_26") (pintype "passive"))
      (node (ref "led1") (pin "g") (pinfunction "g_g") (pintype "passive"))
      (node (ref "led2") (pin "g") (pinfunction "g_g") (pintype "passive"))
      (node (ref "led3") (pin "g") (pinfunction "g_g") (pintype "passive"))
      (node (ref "led4") (pin "g") (pinfunction "g_g") (pintype "passive"))
      (node (ref "led5") (pin "g") (pinfunction "g_g") (pintype "passive"))
    )
    (net (code "66") (name "Net-(U1-WRITE)") (class "Default")
      (node (ref "U1") (pin "8") (pinfunction "WRITE_8") (pintype "passive"))
      (node (ref "U2") (pin "27") (pinfunction "IO_27") (pintype "bidirectional"))
    )
    (net (code "67") (name "Net-(U2E-INPUT{slash}GCLK1)") (class "Default")
      (node (ref "R5") (pin "1") (pinfunction "1_1") (pintype "passive"))
      (node (ref "U2") (pin "37") (pinfunction "INPUT/GCLK1_37") (pintype "input"))
    )
    (net (code "68") (name "Net-(U3-C1+)") (class "Default")
      (node (ref "C3") (pin "1") (pinfunction "1_1") (pintype "passive"))
      (node (ref "U3") (pin "1") (pinfunction "C1+_1") (pintype "passive"))
    )
    (net (code "69") (name "Net-(U3-C1-)") (class "Default")
      (node (ref "C3") (pin "2") (pinfunction "2_2") (pintype "passive"))
      (node (ref "U3") (pin "3") (pinfunction "C1-_3") (pintype "passive"))
    )
    (net (code "70") (name "Net-(U3-C2+)") (class "Default")
      (node (ref "C4") (pin "1") (pinfunction "1_1") (pintype "passive"))
      (node (ref "U3") (pin "4") (pinfunction "C2+_4") (pintype "passive"))
    )
    (net (code "71") (name "Net-(U3-C2-)") (class "Default")
      (node (ref "C4") (pin "2") (pinfunction "2_2") (pintype "passive"))
      (node (ref "U3") (pin "5") (pinfunction "C2-_5") (pintype "passive"))
    )
    (net (code "72") (name "Net-(U3-Vs+)") (class "Default")
      (node (ref "C5") (pin "2") (pinfunction "2_2") (pintype "passive"))
      (node (ref "U3") (pin "2") (pinfunction "Vs+_2") (pintype "passive"))
    )
    (net (code "73") (name "Net-(U3-Vs-)") (class "Default")
      (node (ref "C6") (pin "2") (pinfunction "2_2") (pintype "passive"))
      (node (ref "U3") (pin "6") (pinfunction "Vs-_6") (pintype "passive"))
    )
    (net (code "74") (name "Net-(U5-OUTPUT)") (class "Default")
      (node (ref "R5") (pin "2") (pinfunction "2_2") (pintype "passive"))
      (node (ref "U5") (pin "3") (pinfunction "OUTPUT_3") (pintype "output"))
    )
    (net (code "75") (name "unconnected-(CON1-NC-Pad6)") (class "Default")
      (node (ref "CON1") (pin "6") (pinfunction "NC_6") (pintype "power_in"))
    )
    (net (code "76") (name "unconnected-(CON1-NC-Pad7)") (class "Default")
      (node (ref "CON1") (pin "7") (pinfunction "NC_7") (pintype "passive"))
    )
    (net (code "77") (name "unconnected-(CON1-NC-Pad8)") (class "Default")
      (node (ref "CON1") (pin "8") (pinfunction "NC_8") (pintype "power_in"))
    )
    (net (code "78") (name "unconnected-(U1-DIGIT_6-Pad22)") (class "Default")
      (node (ref "U1") (pin "22") (pinfunction "DIGIT_6_22") (pintype "passive"))
    )
    (net (code "79") (name "unconnected-(U1-DIGIT_7-Pad21)") (class "Default")
      (node (ref "U1") (pin "21") (pinfunction "DIGIT_7_21") (pintype "power_in"))
    )
    (net (code "80") (name "unconnected-(U1-DIGIT_8-Pad18)") (class "Default")
      (node (ref "U1") (pin "18") (pinfunction "DIGIT_8_18") (pintype "passive"))
    )
    (net (code "81") (name "unconnected-(U2B-IO-Pad13)") (class "Default")
      (node (ref "U2") (pin "13") (pinfunction "IO_13") (pintype "bidirectional"))
    )
    (net (code "82") (name "unconnected-(U2B-IO-Pad14)") (class "Default")
      (node (ref "U2") (pin "14") (pinfunction "IO_14") (pintype "bidirectional"))
    )
    (net (code "83") (name "unconnected-(U2E-INPUT{slash}GCLRn-Pad39)") (class "Default")
      (node (ref "U2") (pin "39") (pinfunction "INPUT/GCLRn_39") (pintype "input+no_connect"))
    )
    (net (code "84") (name "unconnected-(U2E-INPUT{slash}OE1-Pad38)") (class "Default")
      (node (ref "U2") (pin "38") (pinfunction "INPUT/OE1_38") (pintype "input+no_connect"))
    )
    (net (code "85") (name "unconnected-(U2E-INPUT{slash}OE2{slash}GCLK2-Pad40)") (class "Default")
      (node (ref "U2") (pin "40") (pinfunction "INPUT/OE2/GCLK2_40") (pintype "input+no_connect"))
    )
    (net (code "86") (name "unconnected-(U3-R1OUT-Pad12)") (class "Default")
      (node (ref "U3") (pin "12") (pinfunction "R1OUT_12") (pintype "output"))
    )
    (net (code "87") (name "unconnected-(U3-T1OUT-Pad14)") (class "Default")
      (node (ref "U3") (pin "14") (pinfunction "T1OUT_14") (pintype "output"))
    )
    (net (code "88") (name "unconnected-(U4-NC-Pad13)") (class "Default")
      (node (ref "U4") (pin "13") (pinfunction "NC_13") (pintype "passive"))
    )
    (net (code "89") (name "unconnected-(U4-NC-Pad16)") (class "Default")
      (node (ref "U4") (pin "16") (pinfunction "NC_16") (pintype "passive"))
    )
    (net (code "90") (name "unconnected-(U4-Pad9)") (class "Default")
      (node (ref "U4") (pin "9") (pinfunction "9_9") (pintype "input"))
    )
    (net (code "91") (name "unconnected-(U4-Pad10)") (class "Default")
      (node (ref "U4") (pin "10") (pinfunction "10_10") (pintype "output"))
    )
    (net (code "92") (name "unconnected-(U4-Pad11)") (class "Default")
      (node (ref "U4") (pin "11") (pinfunction "11_11") (pintype "input"))
    )
    (net (code "93") (name "unconnected-(U4-Pad12)") (class "Default")
      (node (ref "U4") (pin "12") (pinfunction "12_12") (pintype "output"))
    )
    (net (code "94") (name "unconnected-(U5-NC-Pad1)") (class "Default")
      (node (ref "U5") (pin "1") (pinfunction "NC_1") (pintype "passive"))
    )
  )
)
